# VUE_PIC32_v1_0_Motor_2A.net
KiCad netlist of a schematic drawn in Altium Designer
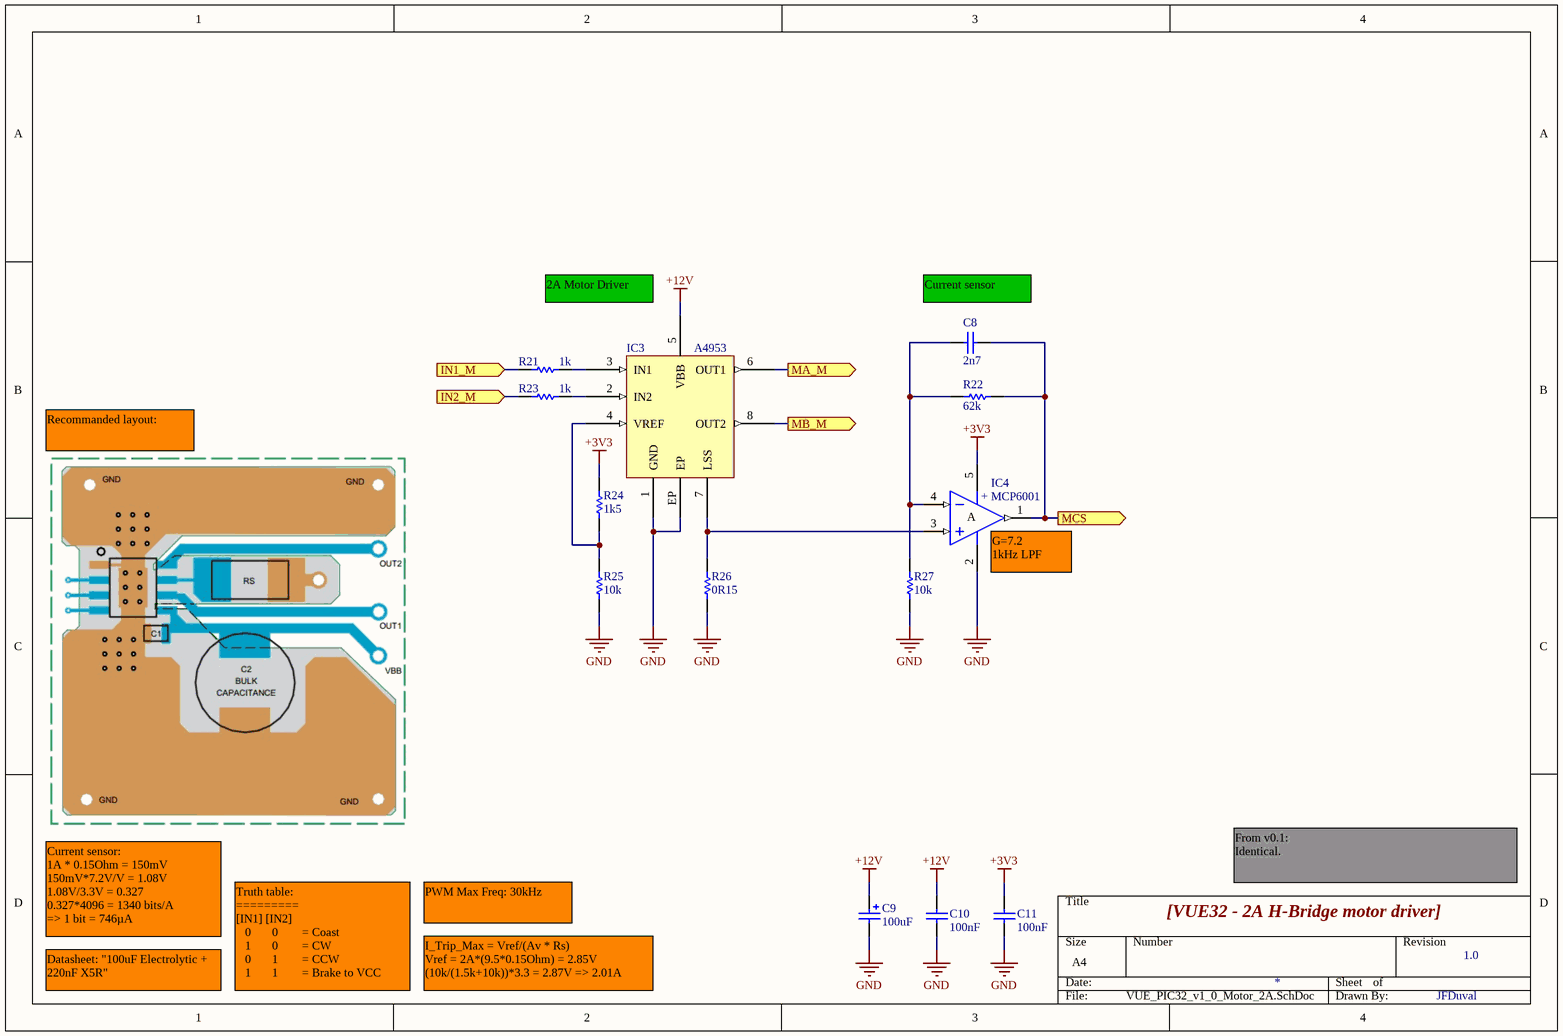
[diagram p0: VUE_PIC32_v1_0_Motor_2A.SchDoc]

(export (version "E")
  (design (tool "Eeschema 10.0.6"))
  (components
    (comp (ref "C8")
      (value "2n7")
      (footprint "0402C")
      (description "CAP CER 2700PF 10V 5% SL 0402")
      (fields (field (name "MFG") "TDK") (field (name "MFGPARTNUMBER") "C1005SL1A272J"))
      (libsource (lib "JFD_Cap") (part "CAP_TDK_C_0402_2n7F_10V"))
    )
    (comp (ref "C9")
      (value "100uF")
      (footprint "CAP_PANA_D_D8")
      (description "CAP ALUM 100UF 25V 20% SMD")
      (fields (field (name "MFG") "Panasonic - ECG") (field (name "MFGPARTNUMBER") "EEE-FK1E101XP"))
      (libsource (lib "JFD_Cap") (part "CAP_PANASONIC_100UF_25V"))
    )
    (comp (ref "C10")
      (value "100nF")
      (footprint "0402C")
      (description "CAP CER 0.1UF 25V Y5V 0402")
      (fields (field (name "MFG") "TDK") (field (name "MFGPARTNUMBER") "C1005Y5V1E104Z"))
      (libsource (lib "JFD_Cap") (part "CAP_TDK_C_0402_100nF_25V"))
    )
    (comp (ref "C11")
      (value "100nF")
      (footprint "0402C")
      (description "CAP CER 0.1UF 25V Y5V 0402")
      (fields (field (name "MFG") "TDK") (field (name "MFGPARTNUMBER") "C1005Y5V1E104Z"))
      (libsource (lib "JFD_Cap") (part "CAP_TDK_C_0402_100nF_25V"))
    )
    (comp (ref "IC3")
      (value "A4953")
      (footprint "SOIC-8_PAD")
      (description "IC PWM MOTOR DVR FULL 8SOIC")
      (fields (field (name "MFG") "Allegro Microsystems Inc") (field (name "MFGPARTNUMBER") "A4953ELJTR-T"))
      (libsource (lib "JFD_IC") (part "IC_ALLEGRO_A4953_MOTOR_HBRIDGE_40V_2A_SOIC8"))
    )
    (comp (ref "IC4")
      (value "MCP6001")
      (footprint "SC70-5")
      (description "IC OPAMP 1.8V 1MHZ SINGLE SC70-5")
      (fields (field (name "MFG") "Microchip Technology") (field (name "MFGPARTNUMBER") "MCP6001T-I/LT"))
      (libsource (lib "JFD_IC") (part "IC_OPA_MICROCHIP_MCP6001_SINGLE_SC70-5"))
    )
    (comp (ref "R21")
      (value "1k")
      (footprint "0402")
      (description "RES 1.00K OHM 1/16W 1% 0402 SMD")
      (fields (field (name "MFG") "Yageo") (field (name "MFGPARTNUMBER") "RC0402FR-071KL"))
      (libsource (lib "JFD_Res") (part "RES_YAGEO_0402_1K_1PCT"))
    )
    (comp (ref "R22")
      (value "62k")
      (footprint "0402")
      (description "RES 62.0K OHM 1/16W 1% 0402 SMD")
      (fields (field (name "MFG") "Yageo") (field (name "MFGPARTNUMBER") "RC0402FR-0762KL"))
      (libsource (lib "JFD_Res") (part "RES_YAGEO_0402_62K_1PCT"))
    )
    (comp (ref "R23")
      (value "1k")
      (footprint "0402")
      (description "RES 1.00K OHM 1/16W 1% 0402 SMD")
      (fields (field (name "MFG") "Yageo") (field (name "MFGPARTNUMBER") "RC0402FR-071KL"))
      (libsource (lib "JFD_Res") (part "RES_YAGEO_0402_1K_1PCT"))
    )
    (comp (ref "R24")
      (value "1k5")
      (footprint "0402")
      (description "RES 1.50K OHM 1/16W 1% 0402 SMD")
      (fields (field (name "MFG") "Yageo") (field (name "MFGPARTNUMBER") "RC0402FR-071K5L"))
      (libsource (lib "JFD_Res") (part "RES_YAGEO_0402_1K5_1PCT"))
    )
    (comp (ref "R25")
      (value "10k")
      (footprint "0402")
      (description "RES 10.0K OHM 1/16W 1% 0402 SMD")
      (fields (field (name "MFG") "Yageo") (field (name "MFGPARTNUMBER") "RC0402FR-0710KL"))
      (libsource (lib "JFD_Res") (part "RES_YAGEO_0402_10K_1PCT"))
    )
    (comp (ref "R26")
      (value "0R15")
      (footprint "2512")
      (description "RES .150 OHM 2W 1% 2512 SMD")
      (fields
        (field (name "MFG") "TT Electronics/IRC")
        (field (name "MFGPARTNUMBER") "LRC-LR2512LF-01-R150-F")
      )
      (libsource (lib "JFD_Res") (part "RES_TT_2512_0R15_1PCT_2W_CURRENT_SENSE"))
    )
    (comp (ref "R27")
      (value "10k")
      (footprint "0402")
      (description "RES 10.0K OHM 1/16W 1% 0402 SMD")
      (fields (field (name "MFG") "Yageo") (field (name "MFGPARTNUMBER") "RC0402FR-0710KL"))
      (libsource (lib "JFD_Res") (part "RES_YAGEO_0402_10K_1PCT"))
    )
  )
  (nets
    (net (code "1") (name "+3V3") (class "Default")
      (node (ref "C11") (pin "2") (pinfunction "2_2") (pintype "passive"))
      (node (ref "IC4") (pin "5") (pinfunction "VDD_5") (pintype "power_in"))
      (node (ref "R24") (pin "2") (pinfunction "2_2") (pintype "passive"))
    )
    (net (code "2") (name "+12V") (class "Default")
      (node (ref "C10") (pin "2") (pinfunction "2_2") (pintype "passive"))
      (node (ref "C9") (pin "A") (pinfunction "1_A") (pintype "passive"))
      (node (ref "IC3") (pin "5") (pinfunction "VBB_5") (pintype "power_in"))
    )
    (net (code "3") (name "/IN1_M") (class "Default")
      (node (ref "R21") (pin "1") (pinfunction "1_1") (pintype "passive"))
    )
    (net (code "4") (name "/IN2_M") (class "Default")
      (node (ref "R23") (pin "1") (pinfunction "1_1") (pintype "passive"))
    )
    (net (code "5") (name "/MA_M") (class "Default")
      (node (ref "IC3") (pin "6") (pinfunction "OUT1_6") (pintype "output"))
    )
    (net (code "6") (name "/MB_M") (class "Default")
      (node (ref "IC3") (pin "8") (pinfunction "OUT2_8") (pintype "output"))
    )
    (net (code "7") (name "/MCS") (class "Default")
      (node (ref "C8") (pin "2") (pinfunction "2_2") (pintype "passive"))
      (node (ref "IC4") (pin "1") (pinfunction "OUT_1") (pintype "output"))
      (node (ref "R22") (pin "1") (pinfunction "1_1") (pintype "passive"))
    )
    (net (code "8") (name "GND") (class "Default")
      (node (ref "C10") (pin "1") (pinfunction "1_1") (pintype "passive"))
      (node (ref "C11") (pin "1") (pinfunction "1_1") (pintype "passive"))
      (node (ref "C9") (pin "K") (pinfunction "2_K") (pintype "passive"))
      (node (ref "IC3") (pin "1") (pinfunction "GND_1") (pintype "power_in"))
      (node (ref "IC3") (pin "EP") (pinfunction "EP_EP") (pintype "power_in"))
      (node (ref "IC4") (pin "2") (pinfunction "VSS_2") (pintype "power_in"))
      (node (ref "R25") (pin "1") (pinfunction "1_1") (pintype "passive"))
      (node (ref "R26") (pin "1") (pinfunction "1_1") (pintype "passive"))
      (node (ref "R27") (pin "1") (pinfunction "1_1") (pintype "passive"))
    )
    (net (code "9") (name "Net-(IC3-IN1)") (class "Default")
      (node (ref "IC3") (pin "3") (pinfunction "IN1_3") (pintype "input"))
      (node (ref "R21") (pin "2") (pinfunction "2_2") (pintype "passive"))
    )
    (net (code "10") (name "Net-(IC3-IN2)") (class "Default")
      (node (ref "IC3") (pin "2") (pinfunction "IN2_2") (pintype "input"))
      (node (ref "R23") (pin "2") (pinfunction "2_2") (pintype "passive"))
    )
    (net (code "11") (name "Net-(IC3-LSS)") (class "Default")
      (node (ref "IC3") (pin "7") (pinfunction "LSS_7") (pintype "power_in"))
      (node (ref "IC4") (pin "3") (pinfunction "IN+_3") (pintype "input"))
      (node (ref "R26") (pin "2") (pinfunction "2_2") (pintype "passive"))
    )
    (net (code "12") (name "Net-(IC3-VREF)") (class "Default")
      (node (ref "IC3") (pin "4") (pinfunction "VREF_4") (pintype "input"))
      (node (ref "R24") (pin "1") (pinfunction "1_1") (pintype "passive"))
      (node (ref "R25") (pin "2") (pinfunction "2_2") (pintype "passive"))
    )
    (net (code "13") (name "Net-(IC4-IN-)") (class "Default")
      (node (ref "C8") (pin "1") (pinfunction "1_1") (pintype "passive"))
      (node (ref "IC4") (pin "4") (pinfunction "IN-_4") (pintype "input"))
      (node (ref "R22") (pin "2") (pinfunction "2_2") (pintype "passive"))
      (node (ref "R27") (pin "2") (pinfunction "2_2") (pintype "passive"))
    )
  )
)
